# SH3_-_17V_BUCK_CONVERTER.net
KiCad netlist of a schematic drawn in Altium Designer
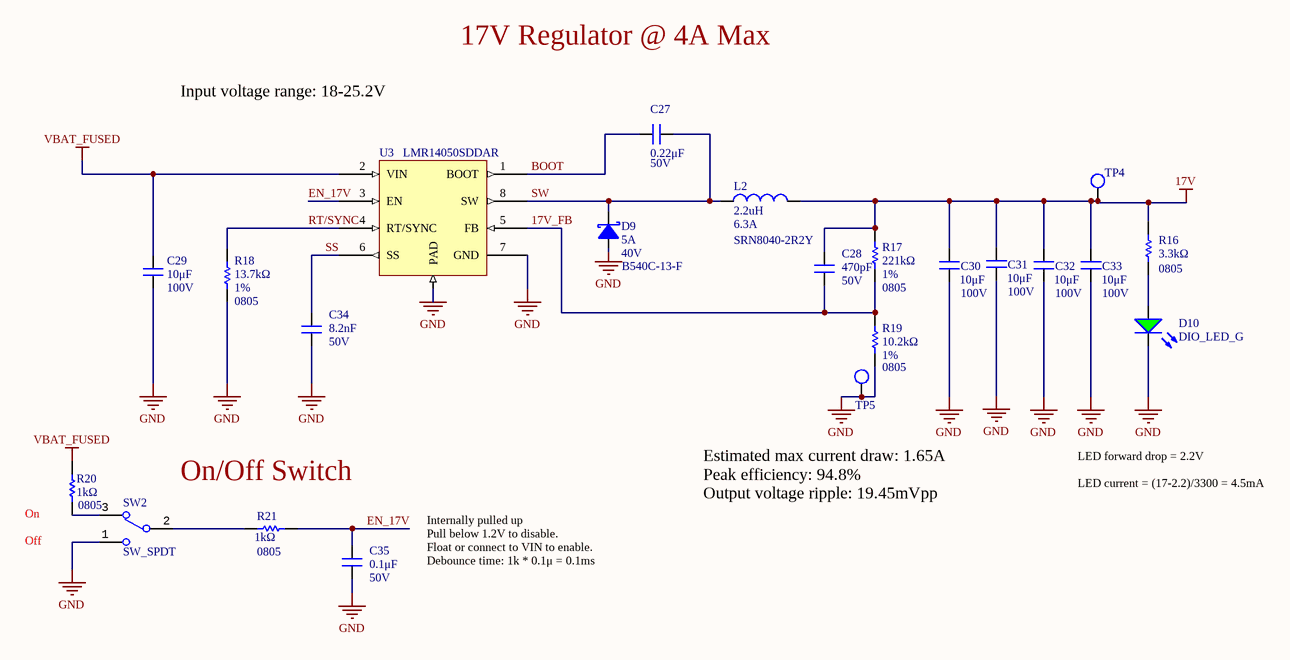
[diagram p0: SH3 - 17V BUCK CONVERTER.SchDoc]

(export (version "E")
  (design (tool "Eeschema 10.0.6"))
  (components
    (comp (ref "C27")
      (value "0.22μF")
      (footprint "CAP2012")
      (description "CAP CER 0.22UF 50V X7R 0805")
      (fields
        (field (name "VOLTAGE RATING") "50V")
        (field (name "LCSC PART #") "C5378")
        (field (name "Comment") "CAP_0.22uF_50V_0805")
      )
      (libsource (lib "UWRT_Schematic_Library_2020") (part "CAP_0.22uF_50V_0805"))
    )
    (comp (ref "C28")
      (value "CAP_470pF_50V_0805")
      (footprint "CAP2012")
      (description "CAP CER 470PF 50V X7R 0805")
      (fields (field (name "VOLTAGE RATING") "50V") (field (name "CAPACITANCE") "470pF"))
      (libsource (lib "UWRT_Schematic_Library_2020") (part "CAP_470pF_50V_0805"))
    )
    (comp (ref "C29")
      (value "10μF")
      (footprint "CAP1210")
      (description "CAP CER 10uF 100V X7S 10% 1210")
      (fields
        (field (name "TOLERANCE") "10%")
        (field (name "VOLTAGE RATING") "100V")
        (field (name "Comment") "CAP_10uF_100V_1210")
      )
      (libsource (lib "UWRT_Schematic_Library_2020") (part "CAP_10uF_100V_1210"))
    )
    (comp (ref "C30")
      (value "10μF")
      (footprint "CAP1210")
      (description "CAP CER 10uF 100V X7S 10% 1210")
      (fields
        (field (name "TOLERANCE") "10%")
        (field (name "VOLTAGE RATING") "100V")
        (field (name "Comment") "CAP_10uF_100V_1210")
      )
      (libsource (lib "UWRT_Schematic_Library_2020") (part "CAP_10uF_100V_1210"))
    )
    (comp (ref "C31")
      (value "10μF")
      (footprint "CAP1210")
      (description "CAP CER 10uF 100V X7S 10% 1210")
      (fields
        (field (name "TOLERANCE") "10%")
        (field (name "VOLTAGE RATING") "100V")
        (field (name "Comment") "CAP_10uF_100V_1210")
      )
      (libsource (lib "UWRT_Schematic_Library_2020") (part "CAP_10uF_100V_1210"))
    )
    (comp (ref "C32")
      (value "10μF")
      (footprint "CAP1210")
      (description "CAP CER 10uF 100V X7S 10% 1210")
      (fields
        (field (name "TOLERANCE") "10%")
        (field (name "VOLTAGE RATING") "100V")
        (field (name "Comment") "CAP_10uF_100V_1210")
      )
      (libsource (lib "UWRT_Schematic_Library_2020") (part "CAP_10uF_100V_1210"))
    )
    (comp (ref "C33")
      (value "10μF")
      (footprint "CAP1210")
      (description "CAP CER 10uF 100V X7S 10% 1210")
      (fields
        (field (name "TOLERANCE") "10%")
        (field (name "VOLTAGE RATING") "100V")
        (field (name "Comment") "CAP_10uF_100V_1210")
      )
      (libsource (lib "UWRT_Schematic_Library_2020") (part "CAP_10uF_100V_1210"))
    )
    (comp (ref "C34")
      (value "CAP_8200pF_50V_0805")
      (footprint "CAP2012")
      (description "CAP CER 8200PF 50V X7R 0805")
      (fields (field (name "VOLTAGE RATING") "50V") (field (name "CAPACITANCE") "8.2nF"))
      (libsource (lib "UWRT_Schematic_Library_2020") (part "CAP_8200pF_50V_0805"))
    )
    (comp (ref "C35")
      (value "0.1μF")
      (footprint "CAP2012")
      (description "CAP CER 0.1UF 50V X7R 0805")
      (fields
        (field (name "VOLTAGE RATING") "50V")
        (field (name "TOLERANCE") "10%")
        (field (name "LCSC PART #") "C49678")
      )
      (libsource (lib "UWRT_Schematic_Library_2020") (part "CAP_0.1uF_50V_0805"))
    )
    (comp (ref "D9")
      (value "B540C-13-F")
      (footprint "DO214AB SMC")
      (description "DIODE SCHOTTKY 40V 5A SMC")
      (fields
        (field (name "MANUFACTURER PART NUMBER 1") "B540C-13-F")
        (field (name "FORWARD CURRENT") "5A")
        (field (name "VOLTAGE") "40V")
        (field (name "LCSC PART #") "C72264")
      )
      (libsource (lib "UWRT_Schematic_Library_2020") (part "B540C-13-F"))
    )
    (comp (ref "D10")
      (value "DIO_LED_G")
      (footprint "LED_0805_GREEN")
      (description "LED GREEN DIFFUSED 0805 SMD")
      (libsource (lib "UWRT_Schematic_Library_2020") (part "DIO_LED_G"))
    )
    (comp (ref "L2")
      (value "SRN8040-2R2Y")
      (footprint "IND_BOURNS_SRN80")
      (description "FIXED IND 2.2UH 6.3A 13 MOHM SMD")
      (fields
        (field (name "MANUFACTURER PART NUMBER 1") "SRN8040-2R2Y")
        (field (name "TOLERANCE") "30%")
        (field (name "INDUCTANCE") "2.2uH")
        (field (name "MAX DC CURRENT") "6.3A")
      )
      (libsource (lib "UWRT_Schematic_Library_2020") (part "SRN8040-2R2Y"))
    )
    (comp (ref "R16")
      (value "RES_3.3kΩ_0805_1%")
      (footprint "RESC0805")
      (description "RES 3.3K OHM 1% 1/8W 0805")
      (fields
        (field (name "TOLERANCE") "1%")
        (field (name "RESISTANCE") "3.3kΩ")
        (field (name "LCSC PART #") "C26010")
        (field (name "PACKAGE/FOOTPRINT") "0805")
      )
      (libsource (lib "UWRT_Schematic_Library_2020") (part "RES_3.3kΩ_0805_1%"))
    )
    (comp (ref "R17")
      (value "RES_221kΩ_0805_1%")
      (footprint "RESC0805")
      (description "RES 221K OHM 1% 1/8W 0805")
      (fields
        (field (name "TOLERANCE") "1%")
        (field (name "RESISTANCE") "221kΩ")
        (field (name "LCSC PART #") "C75431")
        (field (name "PACKAGE/FOOTPRINT") "0805")
      )
      (libsource (lib "UWRT_Schematic_Library_2020") (part "RES_221kΩ_0805_1%"))
    )
    (comp (ref "R18")
      (value "RES_13.7kΩ_0805_1%")
      (footprint "RESC0805")
      (description "RES 13.7K OHM 1% 1/8W 0805")
      (fields
        (field (name "TOLERANCE") "1%")
        (field (name "RESISTANCE") "13.7kΩ")
        (field (name "LCSC PART #") "C17448")
        (field (name "PACKAGE/FOOTPRINT") "0805")
      )
      (libsource (lib "UWRT_Schematic_Library_2020") (part "RES_13.7kΩ_0805_1%"))
    )
    (comp (ref "R19")
      (value "RES_10.2kΩ_0805_1%")
      (footprint "RESC2012X60N")
      (description "RES 10.2K OHM 1% 1/8W 0805")
      (fields
        (field (name "TOLERANCE") "1%")
        (field (name "RESISTANCE") "10.2kΩ")
        (field (name "LCSC PART #") "C17402")
        (field (name "PACKAGE/FOOTPRINT") "0805")
      )
      (libsource (lib "UWRT_Schematic_Library_2020") (part "RES_10.2kΩ_0805_1%"))
    )
    (comp (ref "R20")
      (value "RES_1kΩ_0805_1%")
      (footprint "RESC0805")
      (description "RES 1K OHM 1% 1/8W 0805")
      (fields
        (field (name "RESISTANCE") "1kΩ")
        (field (name "TOLERANCE") "1%")
        (field (name "LCSC PART #") "C17513")
        (field (name "PACKAGE/FOOTPRINT") "0805")
      )
      (libsource (lib "UWRT_Schematic_Library_2020") (part "RES_1kΩ_0805_1%"))
    )
    (comp (ref "R21")
      (value "RES_1kΩ_0805_1%")
      (footprint "RESC0805")
      (description "RES 1K OHM 1% 1/8W 0805")
      (fields
        (field (name "TOLERANCE") "1%")
        (field (name "RESISTANCE") "1kΩ")
        (field (name "LCSC PART #") "C17513")
        (field (name "PACKAGE/FOOTPRINT") "0805")
      )
      (libsource (lib "UWRT_Schematic_Library_2020") (part "RES_1kΩ_0805_1%"))
    )
    (comp (ref "SW2")
      (value "SW_SPDT")
      (footprint "100SP1T1B4M2QE")
      (description "SWITCH TOGGLE SPDT 5A 120V")
      (libsource (lib "UWRT_Schematic_Library_2020") (part "SW_SPDT"))
    )
    (comp (ref "TP4")
      (value "TESTPOINT_LOOP")
      (footprint "TESTPOINT_LOOP")
      (description "PC TEST POINT MINIATURE WHITE")
      (libsource (lib "UWRT_Schematic_Library_2020") (part "TESTPOINT_LOOP"))
    )
    (comp (ref "TP5")
      (value "TESTPOINT_LOOP")
      (footprint "TESTPOINT_LOOP")
      (description "PC TEST POINT MINIATURE WHITE")
      (libsource (lib "UWRT_Schematic_Library_2020") (part "TESTPOINT_LOOP"))
    )
    (comp (ref "U3")
      (value "LMR14050SDDAR")
      (footprint "8-PowerSOIC")
      (description "IC REG BUCK ADJUSTABLE 5A 8SOPWR")
      (fields (field (name "LCSC PART #") "C155484"))
      (libsource (lib "UWRT_Schematic_Library_2020") (part "LMR14050SDDAR"))
    )
  )
  (nets
    (net (code "1") (name "/17V_FB") (class "Default")
      (node (ref "C28") (pin "1") (pinfunction "1_1") (pintype "passive"))
      (node (ref "R17") (pin "1") (pinfunction "1_1") (pintype "passive"))
      (node (ref "R19") (pin "2") (pinfunction "2_2") (pintype "passive"))
      (node (ref "U3") (pin "5") (pinfunction "FB_5") (pintype "input"))
    )
    (net (code "2") (name "/BOOT") (class "Default")
      (node (ref "C27") (pin "2") (pinfunction "2_2") (pintype "passive"))
      (node (ref "U3") (pin "1") (pinfunction "BOOT_1") (pintype "output"))
    )
    (net (code "3") (name "/EN_17V") (class "Default")
      (node (ref "C35") (pin "2") (pinfunction "2_2") (pintype "passive"))
      (node (ref "R21") (pin "2") (pinfunction "2_2") (pintype "passive"))
      (node (ref "U3") (pin "3") (pinfunction "EN_3") (pintype "input"))
    )
    (net (code "4") (name "/RT{slash}SYNC") (class "Default")
      (node (ref "R18") (pin "2") (pinfunction "2_2") (pintype "passive"))
      (node (ref "U3") (pin "4") (pinfunction "RT/SYNC_4") (pintype "input"))
    )
    (net (code "5") (name "/SS") (class "Default")
      (node (ref "C34") (pin "2") (pinfunction "2_2") (pintype "passive"))
      (node (ref "U3") (pin "6") (pinfunction "SS_6") (pintype "output"))
    )
    (net (code "6") (name "/SW") (class "Default")
      (node (ref "C27") (pin "1") (pinfunction "1_1") (pintype "passive"))
      (node (ref "D9") (pin "2") (pinfunction "Cathode_2") (pintype "passive"))
      (node (ref "L2") (pin "1") (pinfunction "1_1") (pintype "passive"))
      (node (ref "U3") (pin "8") (pinfunction "SW_8") (pintype "output"))
    )
    (net (code "7") (name "17V") (class "Default")
      (node (ref "C28") (pin "2") (pinfunction "2_2") (pintype "passive"))
      (node (ref "C30") (pin "2") (pinfunction "2_2") (pintype "passive"))
      (node (ref "C31") (pin "2") (pinfunction "2_2") (pintype "passive"))
      (node (ref "C32") (pin "2") (pinfunction "2_2") (pintype "passive"))
      (node (ref "C33") (pin "2") (pinfunction "2_2") (pintype "passive"))
      (node (ref "L2") (pin "2") (pinfunction "2_2") (pintype "passive"))
      (node (ref "R16") (pin "2") (pinfunction "2_2") (pintype "passive"))
      (node (ref "R17") (pin "2") (pinfunction "2_2") (pintype "passive"))
      (node (ref "TP4") (pin "1") (pintype "passive"))
    )
    (net (code "8") (name "GND") (class "Default")
      (node (ref "C29") (pin "2") (pinfunction "2_2") (pintype "passive"))
      (node (ref "C30") (pin "1") (pinfunction "1_1") (pintype "passive"))
      (node (ref "C31") (pin "1") (pinfunction "1_1") (pintype "passive"))
      (node (ref "C32") (pin "1") (pinfunction "1_1") (pintype "passive"))
      (node (ref "C33") (pin "1") (pinfunction "1_1") (pintype "passive"))
      (node (ref "C34") (pin "1") (pinfunction "1_1") (pintype "passive"))
      (node (ref "C35") (pin "1") (pinfunction "1_1") (pintype "passive"))
      (node (ref "D10") (pin "2") (pinfunction "K_2") (pintype "passive"))
      (node (ref "D9") (pin "1") (pinfunction "Anode_1") (pintype "passive"))
      (node (ref "R18") (pin "1") (pinfunction "1_1") (pintype "passive"))
      (node (ref "R19") (pin "1") (pinfunction "1_1") (pintype "passive"))
      (node (ref "SW2") (pin "1") (pinfunction "1_1") (pintype "passive"))
      (node (ref "TP5") (pin "1") (pintype "passive"))
      (node (ref "U3") (pin "7") (pinfunction "GND_7") (pintype "power_in"))
      (node (ref "U3") (pin "9") (pinfunction "PAD_9") (pintype "input"))
    )
    (net (code "9") (name "Net-(D10-A)") (class "Default")
      (node (ref "D10") (pin "1") (pinfunction "A_1") (pintype "passive"))
      (node (ref "R16") (pin "1") (pinfunction "1_1") (pintype "passive"))
    )
    (net (code "10") (name "Net-(R20-Pad1)") (class "Default")
      (node (ref "R20") (pin "1") (pinfunction "1_1") (pintype "passive"))
      (node (ref "SW2") (pin "3") (pinfunction "3_3") (pintype "passive"))
    )
    (net (code "11") (name "Net-(R21-Pad1)") (class "Default")
      (node (ref "R21") (pin "1") (pinfunction "1_1") (pintype "passive"))
      (node (ref "SW2") (pin "2") (pinfunction "2_2") (pintype "passive"))
    )
    (net (code "12") (name "VBAT_FUSED") (class "Default")
      (node (ref "C29") (pin "1") (pinfunction "1_1") (pintype "passive"))
      (node (ref "R20") (pin "2") (pinfunction "2_2") (pintype "passive"))
      (node (ref "U3") (pin "2") (pinfunction "VIN_2") (pintype "input"))
    )
  )
)
